# LM_And_Busler_CAM.net
KiCad netlist of a schematic drawn in Altium Designer
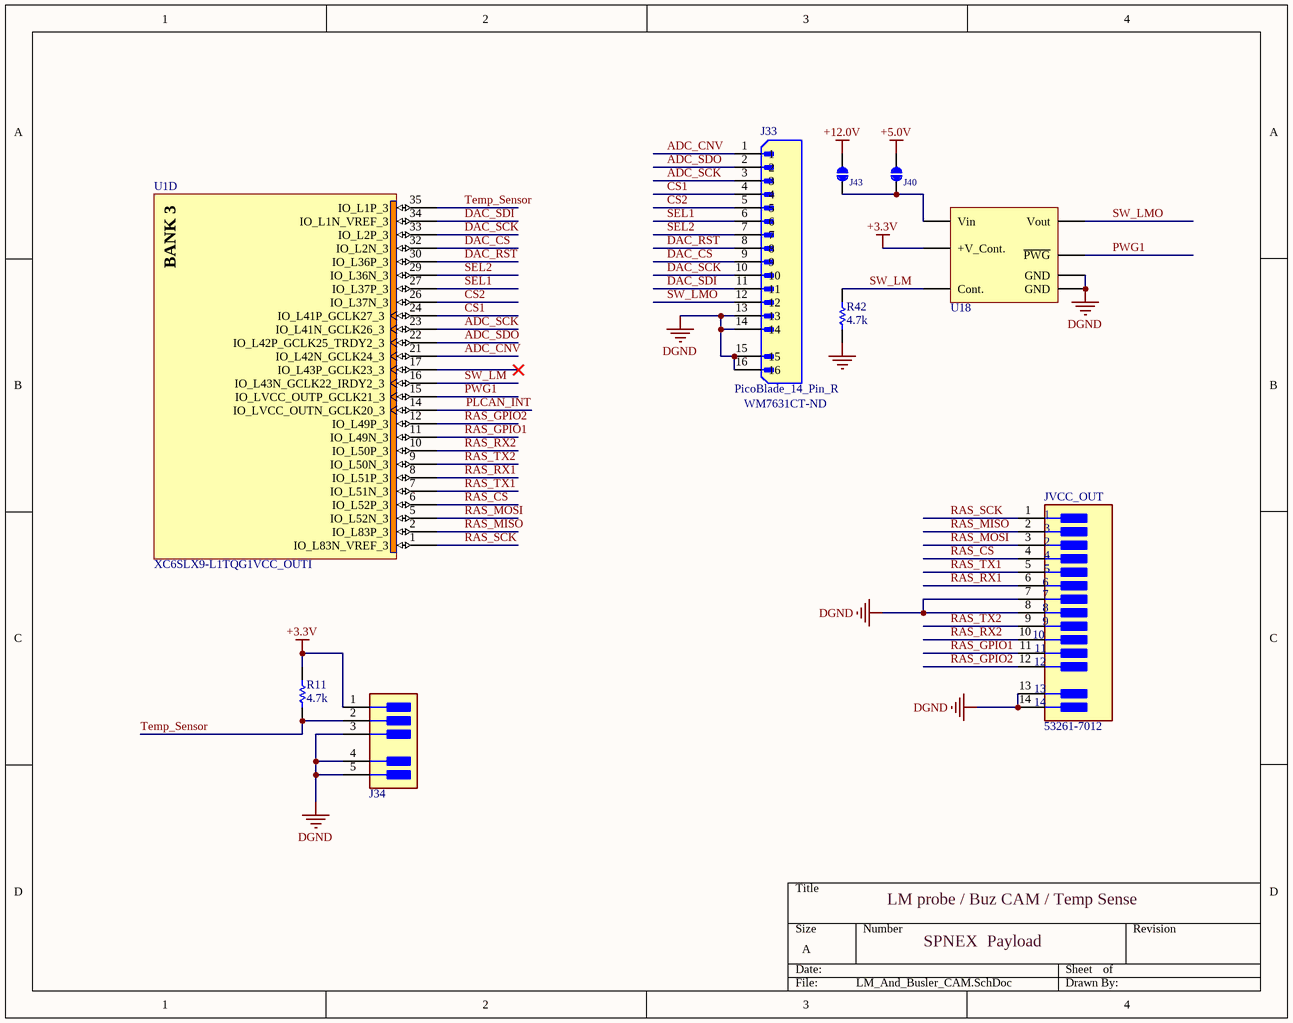
[diagram p0: LM_And_Busler_CAM.SchDoc]

(export (version "E")
  (design (tool "Eeschema 10.0.6"))
  (components
    (comp (ref "J33")
      (value "PicoBlade_14_Pin_R")
      (footprint "PicoBlade_14_pin_R")
      (description "1.25mm Pitch PicoBlade Header, Surface Mount, Right Angle, Lead-Free, 14 Circuits")
      (fields
        (field (name "MANUFACTURER") "Molex")
        (field (name "MANUFACTURER PART NUMBER") "53261-1471")
        (field (name "SUPPLIER PART NUMBER 1") "WM7631CT-ND")
      )
      (libsource (lib "Probe") (part "PicoBlade_14_Pin_R"))
    )
    (comp (ref "J34")
      (value "53261-0371")
      (footprint "FP-53261-0371-MFG")
      (description "Conn Shrouded Header HDR 3 POS 1.25mm Solder RA SMD PicoBlade™ Embossed T/R")
      (fields (field (name "MANUFACTURER") "Molex"))
      (libsource (lib "Spnex_library") (part "0532610371"))
    )
    (comp (ref "J40")
      (value "JUMPER")
      (footprint "SJMP")
      (description "OPTION SELECTION PAD")
      (libsource (lib "Kh_Lib") (part "JUMPER"))
    )
    (comp (ref "J43")
      (value "JUMPER")
      (footprint "SJMP")
      (description "OPTION SELECTION PAD")
      (libsource (lib "Kh_Lib") (part "JUMPER"))
    )
    (comp (ref "JVCC_OUT")
      (value "53261-7012")
      (footprint "MOLEX_12RA")
      (fields (field (name "MANUFACTURER") "Molex"))
      (libsource (lib "Spnex_library") (part "53261-7012"))
    )
    (comp (ref "R11")
      (value "RES_4.7K_0.1W_0603")
      (footprint "0603RES")
      (description "Resistor")
      (fields
        (field (name "MANUFACTURER") "Stackpole Electronics Inc.")
        (field (name "MANUFACTURER PART NUMBER") "RMCF0603JT4K70")
        (field (name "RESISTANCE (OHMS)") "4.7k")
      )
      (libsource (lib "Spnex_library") (part "RES_4.7K_0.1W_0603"))
    )
    (comp (ref "R42")
      (value "RES_4.7K_0.1W_0603")
      (footprint "0603RES")
      (description "Resistor")
      (fields
        (field (name "MANUFACTURER") "Stackpole Electronics Inc.")
        (field (name "MANUFACTURER PART NUMBER") "RMCF0603JT4K70")
        (field (name "RESISTANCE (OHMS)") "4.7k")
      )
      (libsource (lib "Spnex_lib") (part "RES_4.7K_0.1W_0603"))
    )
    (comp (ref "U1")
      (value "XC6SLX9-L1TQG1VCC_OUTI")
      (footprint "TQG144_M")
      (fields (field (name "PUBLISHER") "Altium Limited"))
      (libsource (lib "Spnex_lib") (part "XC6SLX9-L1TQG144I"))
    )
    (comp (ref "U18")
      (value "LTC3461 module")
      (footprint "OCPfootprint")
      (libsource (lib "Kh_Lib") (part "OCP_Module"))
    )
  )
  (nets
    (net (code "1") (name "+3.3V") (class "Default")
      (node (ref "J34") (pin "1") (pinfunction "1_1") (pintype "passive"))
      (node (ref "R11") (pin "2") (pinfunction "2_2") (pintype "passive"))
      (node (ref "U18") (pin "5") (pinfunction "+V_Cont._5") (pintype "passive"))
    )
    (net (code "2") (name "+5.0V") (class "Default")
      (node (ref "J40") (pin "2") (pinfunction "2_2") (pintype "passive"))
    )
    (net (code "3") (name "+12.0V") (class "Default")
      (node (ref "J43") (pin "2") (pinfunction "2_2") (pintype "passive"))
    )
    (net (code "4") (name "/ADC_CNV") (class "Default")
      (node (ref "J33") (pin "1") (pinfunction "1_1") (pintype "passive"))
      (node (ref "U1") (pin "21") (pinfunction "IO_L42N_GCLK24_3_21") (pintype "bidirectional"))
    )
    (net (code "5") (name "/ADC_SCK") (class "Default")
      (node (ref "J33") (pin "3") (pinfunction "3_3") (pintype "passive"))
      (node (ref "U1") (pin "23") (pinfunction "IO_L41N_GCLK26_3_23") (pintype "bidirectional"))
    )
    (net (code "6") (name "/ADC_SDO") (class "Default")
      (node (ref "J33") (pin "2") (pinfunction "2_2") (pintype "passive"))
      (node (ref "U1") (pin "22") (pinfunction "IO_L42P_GCLK25_TRDY2_3_22") (pintype "bidirectional"))
    )
    (net (code "7") (name "/CS1") (class "Default")
      (node (ref "J33") (pin "4") (pinfunction "4_4") (pintype "passive"))
      (node (ref "U1") (pin "24") (pinfunction "IO_L41P_GCLK27_3_24") (pintype "bidirectional"))
    )
    (net (code "8") (name "/CS2") (class "Default")
      (node (ref "J33") (pin "5") (pinfunction "5_5") (pintype "passive"))
      (node (ref "U1") (pin "26") (pinfunction "IO_L37N_3_26") (pintype "bidirectional"))
    )
    (net (code "9") (name "/DAC_CS") (class "Default")
      (node (ref "J33") (pin "9") (pinfunction "9_9") (pintype "passive"))
      (node (ref "U1") (pin "32") (pinfunction "IO_L2N_3_32") (pintype "bidirectional"))
    )
    (net (code "10") (name "/DAC_RST") (class "Default")
      (node (ref "J33") (pin "8") (pinfunction "8_8") (pintype "passive"))
      (node (ref "U1") (pin "30") (pinfunction "IO_L36P_3_30") (pintype "bidirectional"))
    )
    (net (code "11") (name "/DAC_SCK") (class "Default")
      (node (ref "J33") (pin "10") (pinfunction "10_10") (pintype "passive"))
      (node (ref "U1") (pin "33") (pinfunction "IO_L2P_3_33") (pintype "bidirectional"))
    )
    (net (code "12") (name "/DAC_SDI") (class "Default")
      (node (ref "J33") (pin "11") (pinfunction "11_11") (pintype "passive"))
      (node (ref "U1") (pin "34") (pinfunction "IO_L1N_VREF_3_34") (pintype "bidirectional"))
    )
    (net (code "13") (name "/PLCAN_INT") (class "Default")
      (node (ref "U1") (pin "14") (pinfunction "IO_LVCC_OUTN_GCLK20_3_14") (pintype "bidirectional"))
    )
    (net (code "14") (name "/PWG1") (class "Default")
      (node (ref "U1") (pin "15") (pinfunction "IO_LVCC_OUTP_GCLK21_3_15") (pintype "bidirectional"))
      (node (ref "U18") (pin "7") (pinfunction "~{PWG}_7") (pintype "passive"))
    )
    (net (code "15") (name "/RAS_CS") (class "Default")
      (node (ref "JVCC_OUT") (pin "4") (pinfunction "4_4") (pintype "passive"))
      (node (ref "U1") (pin "6") (pinfunction "IO_L52P_3_6") (pintype "bidirectional"))
    )
    (net (code "16") (name "/RAS_GPIO1") (class "Default")
      (node (ref "JVCC_OUT") (pin "11") (pinfunction "11_11") (pintype "passive"))
      (node (ref "U1") (pin "11") (pinfunction "IO_L49N_3_11") (pintype "bidirectional"))
    )
    (net (code "17") (name "/RAS_GPIO2") (class "Default")
      (node (ref "JVCC_OUT") (pin "12") (pinfunction "12_12") (pintype "passive"))
      (node (ref "U1") (pin "12") (pinfunction "IO_L49P_3_12") (pintype "bidirectional"))
    )
    (net (code "18") (name "/RAS_MISO") (class "Default")
      (node (ref "JVCC_OUT") (pin "2") (pinfunction "2_2") (pintype "passive"))
      (node (ref "U1") (pin "2") (pinfunction "IO_L83P_3_2") (pintype "bidirectional"))
    )
    (net (code "19") (name "/RAS_MOSI") (class "Default")
      (node (ref "JVCC_OUT") (pin "3") (pinfunction "3_3") (pintype "passive"))
      (node (ref "U1") (pin "5") (pinfunction "IO_L52N_3_5") (pintype "bidirectional"))
    )
    (net (code "20") (name "/RAS_RX1") (class "Default")
      (node (ref "JVCC_OUT") (pin "6") (pinfunction "6_6") (pintype "passive"))
      (node (ref "U1") (pin "8") (pinfunction "IO_L51P_3_8") (pintype "bidirectional"))
    )
    (net (code "21") (name "/RAS_RX2") (class "Default")
      (node (ref "JVCC_OUT") (pin "10") (pinfunction "10_10") (pintype "passive"))
      (node (ref "U1") (pin "10") (pinfunction "IO_L50P_3_10") (pintype "bidirectional"))
    )
    (net (code "22") (name "/RAS_SCK") (class "Default")
      (node (ref "JVCC_OUT") (pin "1") (pinfunction "1_1") (pintype "passive"))
      (node (ref "U1") (pin "1") (pinfunction "IO_L83N_VREF_3_1") (pintype "bidirectional"))
    )
    (net (code "23") (name "/RAS_TX1") (class "Default")
      (node (ref "JVCC_OUT") (pin "5") (pinfunction "5_5") (pintype "passive"))
      (node (ref "U1") (pin "7") (pinfunction "IO_L51N_3_7") (pintype "bidirectional"))
    )
    (net (code "24") (name "/RAS_TX2") (class "Default")
      (node (ref "JVCC_OUT") (pin "9") (pinfunction "9_9") (pintype "passive"))
      (node (ref "U1") (pin "9") (pinfunction "IO_L50N_3_9") (pintype "bidirectional"))
    )
    (net (code "25") (name "/SEL1") (class "Default")
      (node (ref "J33") (pin "6") (pinfunction "6_6") (pintype "passive"))
      (node (ref "U1") (pin "27") (pinfunction "IO_L37P_3_27") (pintype "bidirectional"))
    )
    (net (code "26") (name "/SEL2") (class "Default")
      (node (ref "J33") (pin "7") (pinfunction "7_7") (pintype "passive"))
      (node (ref "U1") (pin "29") (pinfunction "IO_L36N_3_29") (pintype "bidirectional"))
    )
    (net (code "27") (name "/SW_LM") (class "Default")
      (node (ref "R42") (pin "1") (pinfunction "1_1") (pintype "passive"))
      (node (ref "U1") (pin "16") (pinfunction "IO_L43N_GCLK22_IRDY2_3_16") (pintype "bidirectional"))
      (node (ref "U18") (pin "6") (pinfunction "Cont._6") (pintype "passive"))
    )
    (net (code "28") (name "/SW_LMO") (class "Default")
      (node (ref "J33") (pin "12") (pinfunction "12_12") (pintype "passive"))
      (node (ref "U18") (pin "3") (pinfunction "Vout_3") (pintype "passive"))
    )
    (net (code "29") (name "/Temp_Sensor") (class "Default")
      (node (ref "J34") (pin "2") (pinfunction "2_2") (pintype "passive"))
      (node (ref "R11") (pin "1") (pinfunction "1_1") (pintype "passive"))
      (node (ref "U1") (pin "35") (pinfunction "IO_L1P_3_35") (pintype "bidirectional"))
    )
    (net (code "30") (name "DGND") (class "Default")
      (node (ref "J33") (pin "13") (pinfunction "13_13") (pintype "passive"))
      (node (ref "J33") (pin "14") (pinfunction "14_14") (pintype "passive"))
      (node (ref "J33") (pin "15") (pinfunction "15_15") (pintype "passive"))
      (node (ref "J33") (pin "16") (pinfunction "16_16") (pintype "passive"))
      (node (ref "J34") (pin "3") (pinfunction "3_3") (pintype "passive"))
      (node (ref "J34") (pin "4") (pinfunction "4_4") (pintype "passive"))
      (node (ref "J34") (pin "5") (pinfunction "5_5") (pintype "passive"))
      (node (ref "JVCC_OUT") (pin "13") (pinfunction "MNT_1_13") (pintype "passive"))
      (node (ref "JVCC_OUT") (pin "14") (pinfunction "MNT_2_14") (pintype "passive"))
      (node (ref "JVCC_OUT") (pin "7") (pinfunction "7_7") (pintype "passive"))
      (node (ref "JVCC_OUT") (pin "8") (pinfunction "8_8") (pintype "passive"))
      (node (ref "R42") (pin "2") (pinfunction "2_2") (pintype "passive"))
      (node (ref "U18") (pin "2") (pinfunction "GND_2") (pintype "passive"))
      (node (ref "U18") (pin "4") (pinfunction "GND_4") (pintype "passive"))
    )
    (net (code "31") (name "Net-(U18-Vin)") (class "Default")
      (node (ref "J40") (pin "1") (pinfunction "1_1") (pintype "passive"))
      (node (ref "J43") (pin "1") (pinfunction "1_1") (pintype "passive"))
      (node (ref "U18") (pin "1") (pinfunction "Vin_1") (pintype "passive"))
    )
    (net (code "32") (name "unconnected-(U1D-IO_L43P_GCLK23_3-Pad17)") (class "Default")
      (node (ref "U1") (pin "17") (pinfunction "IO_L43P_GCLK23_3_17") (pintype "bidirectional+no_connect"))
    )
  )
)
